# WalkerStalkerv20.net
KiCad netlist of a schematic drawn in EAGLE
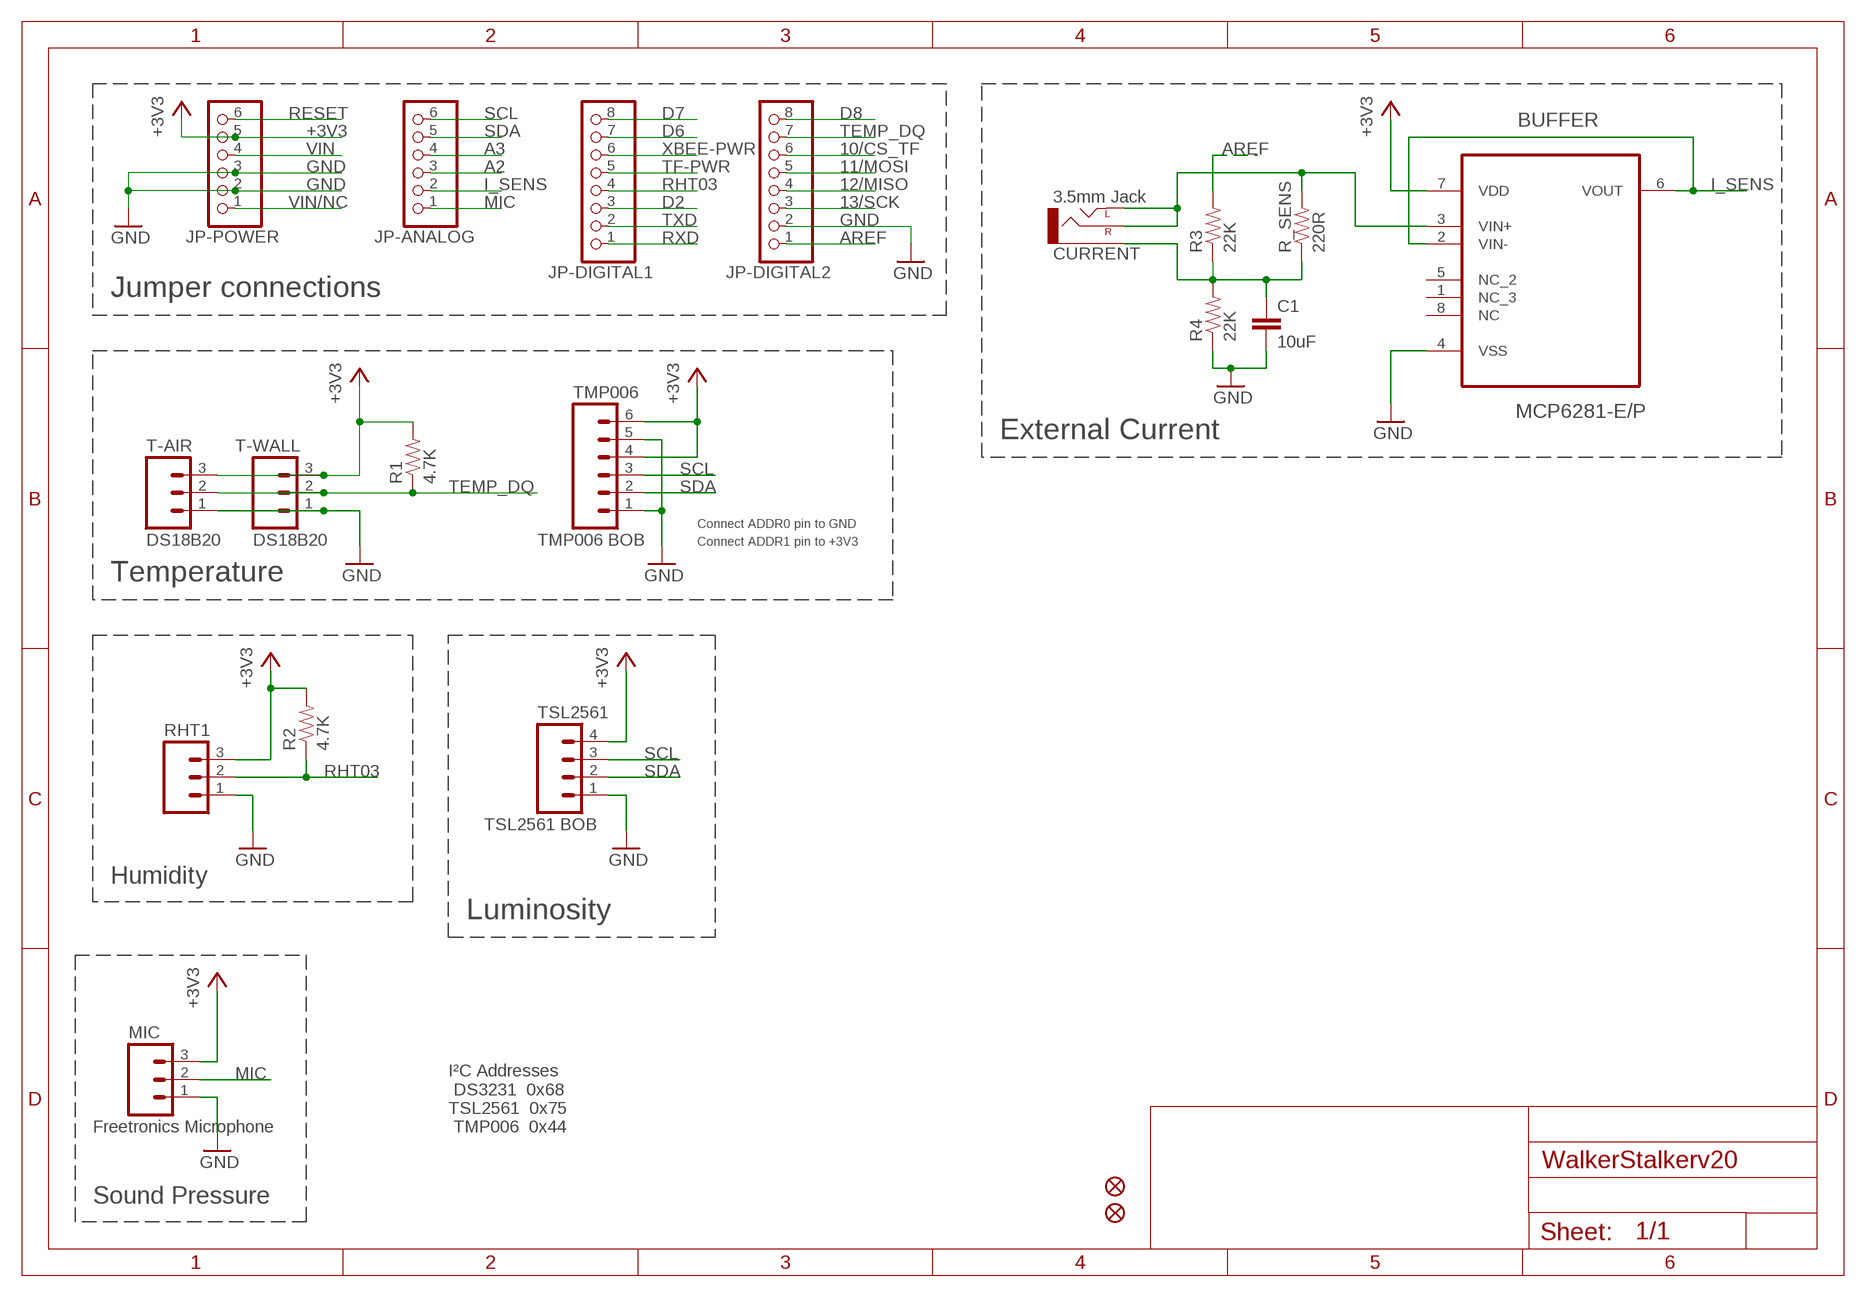
[diagram p0: schematic, sheet 1, part 1 of 2]
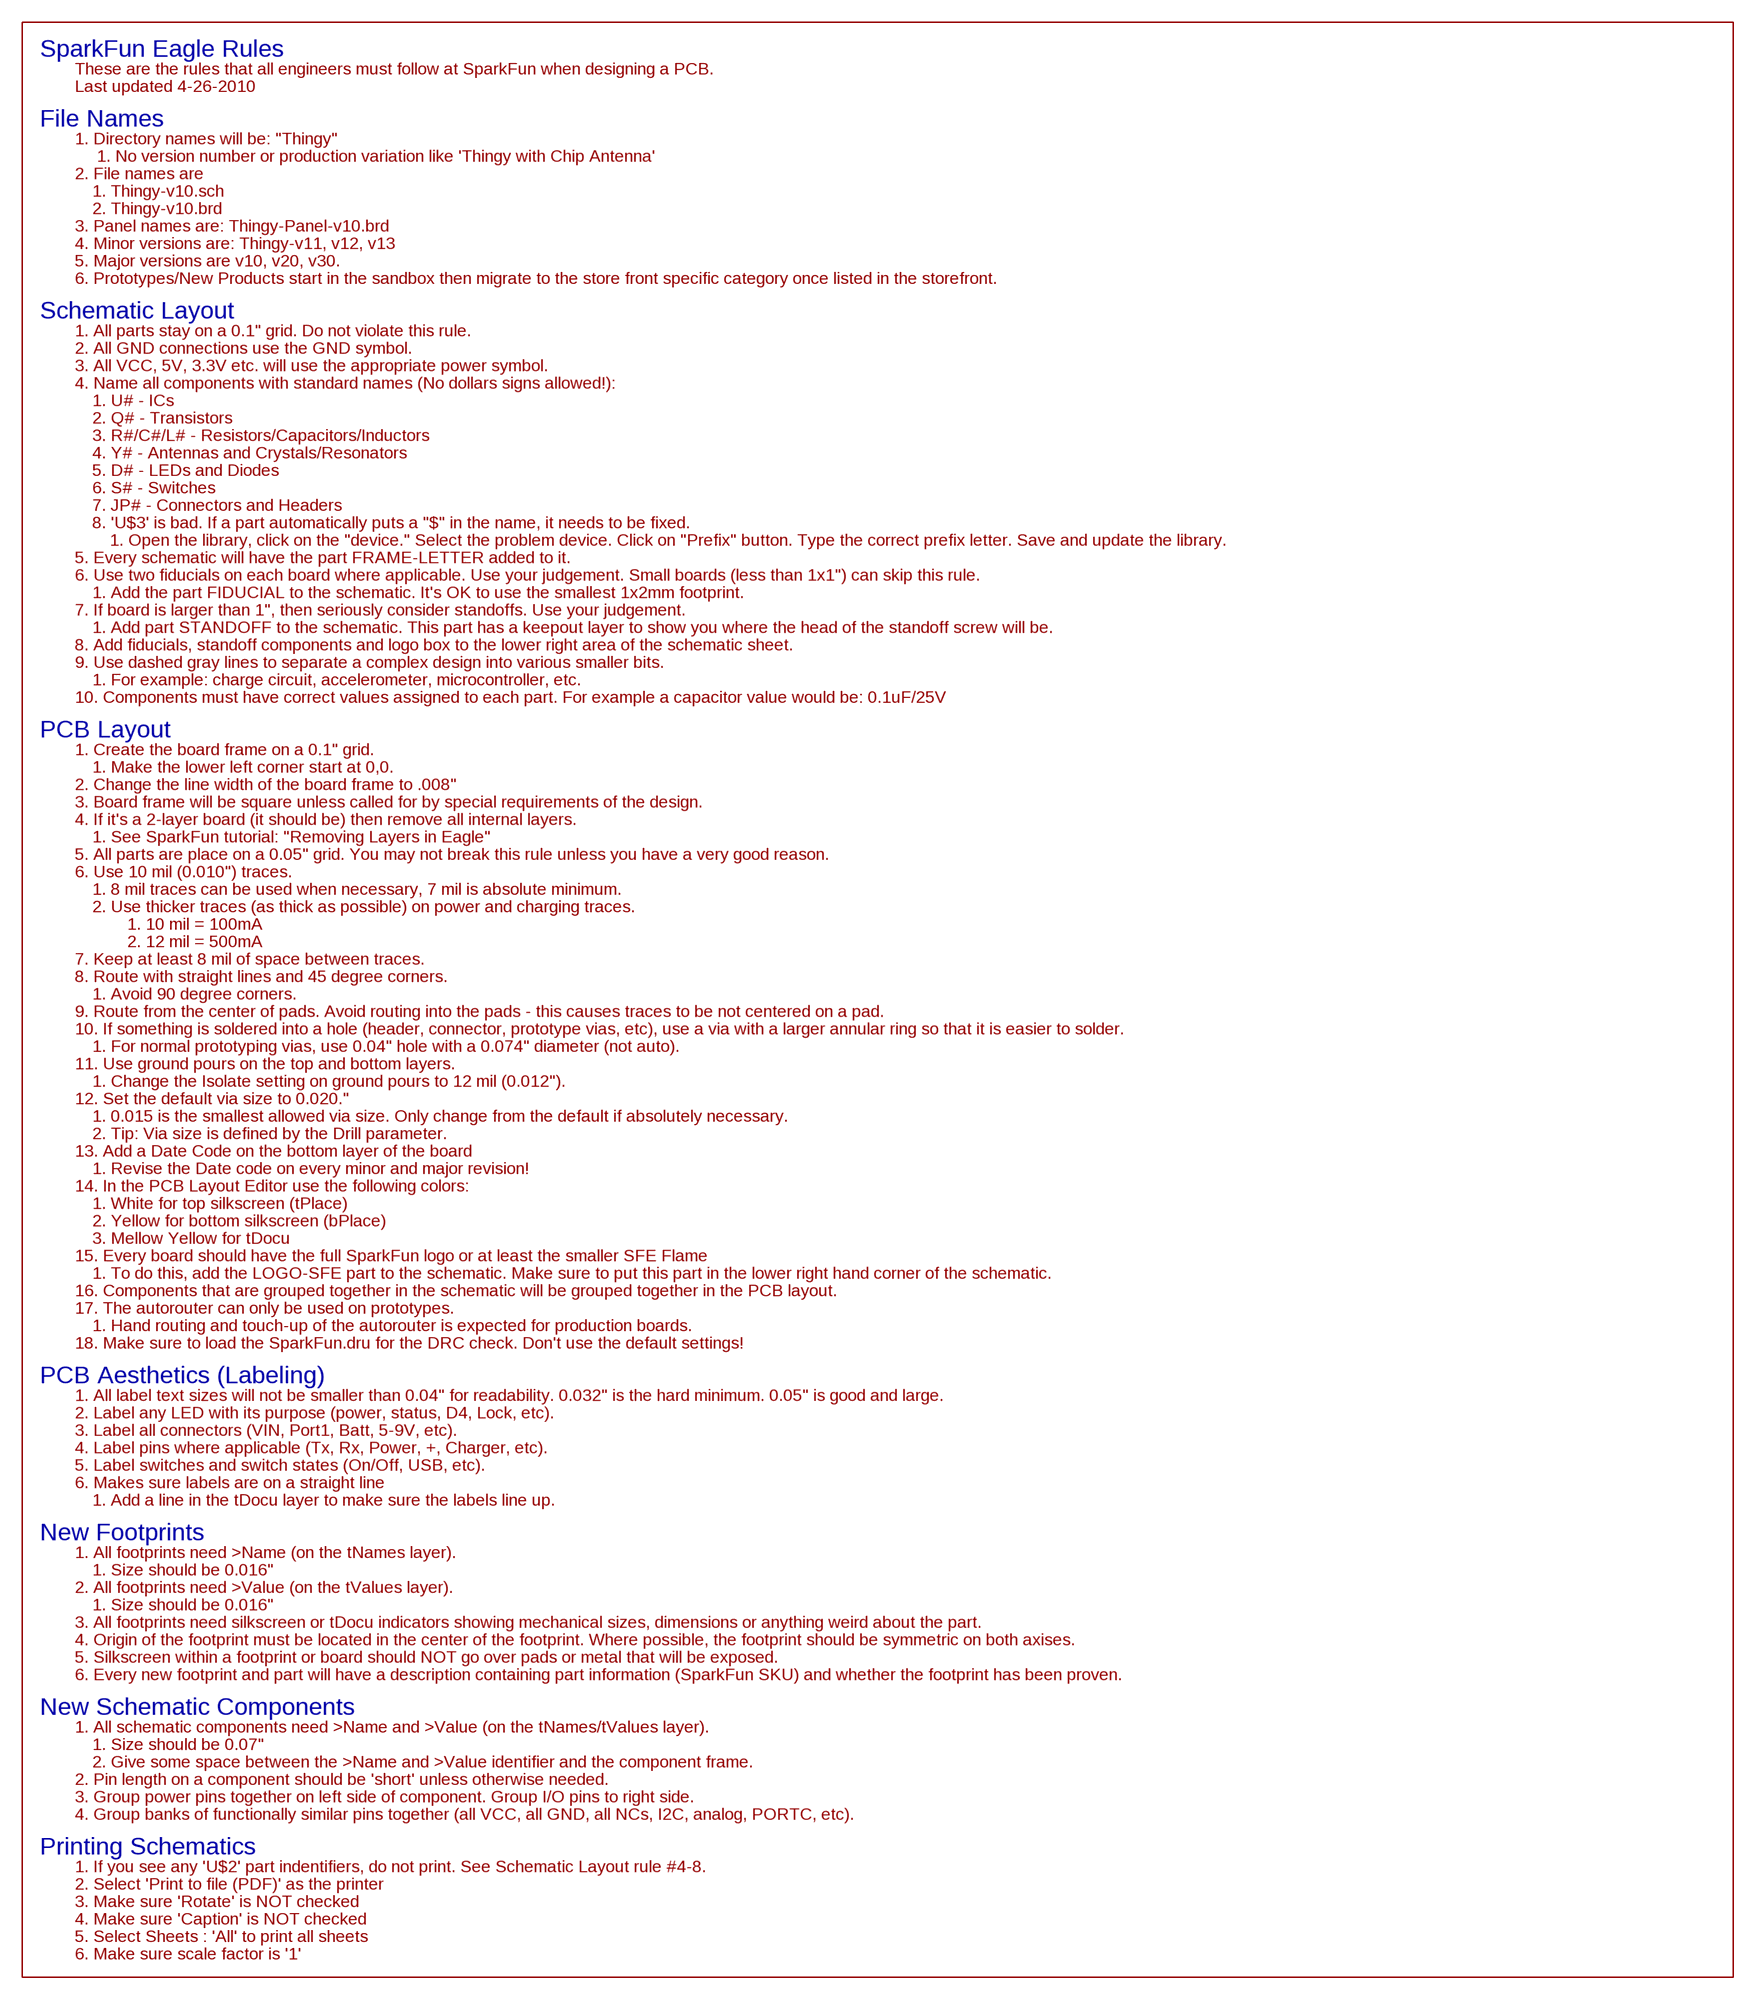
[diagram p1: schematic, sheet 1, part 2 of 2]

(export (version "E")
  (design (tool "Eeschema 10.0.6"))
  (components
    (comp (ref "BUFFER")
      (value "MCP6281-E/P")
      (footprint "eagle-import:DIP254P762X432-8")
      (libsource (lib "eagle-import") (part "MCP6281-E/P"))
    )
    (comp (ref "C1")
      (value "10uF")
      (footprint "eagle-import:1206")
      (libsource (lib "eagle-import") (part "CAP1206"))
    )
    (comp (ref "CURRENT")
      (value "3.5mm Jack")
      (footprint "eagle-import:AUDIO-JACK")
      (libsource (lib "eagle-import") (part "AUDIO-JACKPTH"))
    )
    (comp (ref "FID1")
      (value "FIDUCIAL1.5X3")
      (footprint "eagle-import:FIDUCIAL-1.5X3")
      (libsource (lib "eagle-import") (part "FIDUCIAL1.5X3"))
    )
    (comp (ref "FID2")
      (value "FIDUCIAL1.5X3")
      (footprint "eagle-import:FIDUCIAL-1.5X3")
      (libsource (lib "eagle-import") (part "FIDUCIAL1.5X3"))
    )
    (comp (ref "JP-ANALOG")
      (value "PINHD-1X6CB")
      (footprint "eagle-import:1X06-CLEANBIG")
      (libsource (lib "eagle-import") (part "PINHD-1X6CB"))
    )
    (comp (ref "JP-DIGITAL1")
      (value "PINHD-1X8CLEANBIG")
      (footprint "eagle-import:1X08-CLEANBIG")
      (libsource (lib "eagle-import") (part "PINHD-1X8CLEANBIG"))
    )
    (comp (ref "JP-DIGITAL2")
      (value "PINHD-1X8CLEANBIG")
      (footprint "eagle-import:1X08-CLEANBIG")
      (libsource (lib "eagle-import") (part "PINHD-1X8CLEANBIG"))
    )
    (comp (ref "JP-POWER")
      (value "PINHD-1X6CB")
      (footprint "eagle-import:1X06-CLEANBIG")
      (libsource (lib "eagle-import") (part "PINHD-1X6CB"))
    )
    (comp (ref "MIC")
      (value "Freetronics Microphone")
      (footprint "eagle-import:1X03")
      (libsource (lib "eagle-import") (part "M03PTH"))
    )
    (comp (ref "R1")
      (value "4.7K")
      (footprint "eagle-import:1206")
      (libsource (lib "eagle-import") (part "RESISTOR1206"))
    )
    (comp (ref "R2")
      (value "4.7K")
      (footprint "eagle-import:1206")
      (libsource (lib "eagle-import") (part "RESISTOR1206"))
    )
    (comp (ref "R3")
      (value "22K")
      (footprint "eagle-import:1206")
      (libsource (lib "eagle-import") (part "RESISTOR1206"))
    )
    (comp (ref "R4")
      (value "22K")
      (footprint "eagle-import:1206")
      (libsource (lib "eagle-import") (part "RESISTOR1206"))
    )
    (comp (ref "RHT1")
      (value "RHT03")
      (footprint "eagle-import:1X03")
      (libsource (lib "eagle-import") (part "M03PTH"))
    )
    (comp (ref "R_SENS")
      (value "220R")
      (footprint "eagle-import:1206")
      (libsource (lib "eagle-import") (part "RESISTOR1206"))
    )
    (comp (ref "T-AIR")
      (value "DS18B20")
      (footprint "eagle-import:1X03")
      (libsource (lib "eagle-import") (part "M03PTH"))
    )
    (comp (ref "T-WALL")
      (value "DS18B20")
      (footprint "eagle-import:1X03")
      (libsource (lib "eagle-import") (part "M03PTH"))
    )
    (comp (ref "TMP006")
      (value "TMP006 BOB")
      (footprint "eagle-import:1X06")
      (libsource (lib "eagle-import") (part "M06SIP"))
    )
    (comp (ref "TSL2561")
      (value "TSL2561 BOB")
      (footprint "eagle-import:1X04")
      (libsource (lib "eagle-import") (part "M04PTH"))
    )
  )
  (nets
    (net (code "1") (name "+3V3") (class "Default")
      (node (ref "BUFFER") (pin "7") (pinfunction "VDD_7") (pintype "power_in"))
      (node (ref "JP-POWER") (pin "5") (pinfunction "5_5") (pintype "passive"))
      (node (ref "MIC") (pin "3") (pinfunction "3_3") (pintype "passive"))
      (node (ref "R1") (pin "2") (pinfunction "2_2") (pintype "passive"))
      (node (ref "R2") (pin "2") (pinfunction "2_2") (pintype "passive"))
      (node (ref "RHT1") (pin "3") (pinfunction "3_3") (pintype "passive"))
      (node (ref "T-AIR") (pin "3") (pinfunction "3_3") (pintype "passive"))
      (node (ref "T-WALL") (pin "3") (pinfunction "3_3") (pintype "passive"))
      (node (ref "TMP006") (pin "4") (pinfunction "4_4") (pintype "passive"))
      (node (ref "TMP006") (pin "6") (pinfunction "6_6") (pintype "passive"))
      (node (ref "TSL2561") (pin "4") (pinfunction "4_4") (pintype "passive"))
    )
    (net (code "2") (name "/10{slash}CS_TF") (class "Default")
      (node (ref "JP-DIGITAL2") (pin "6") (pinfunction "6_6") (pintype "passive"))
    )
    (net (code "3") (name "/11{slash}MOSI") (class "Default")
      (node (ref "JP-DIGITAL2") (pin "5") (pinfunction "5_5") (pintype "passive"))
    )
    (net (code "4") (name "/12{slash}MISO") (class "Default")
      (node (ref "JP-DIGITAL2") (pin "4") (pinfunction "4_4") (pintype "passive"))
    )
    (net (code "5") (name "/13{slash}SCK") (class "Default")
      (node (ref "JP-DIGITAL2") (pin "3") (pinfunction "3_3") (pintype "passive"))
    )
    (net (code "6") (name "/A2") (class "Default")
      (node (ref "JP-ANALOG") (pin "3") (pinfunction "3_3") (pintype "passive"))
    )
    (net (code "7") (name "/A3") (class "Default")
      (node (ref "JP-ANALOG") (pin "4") (pinfunction "4_4") (pintype "passive"))
    )
    (net (code "8") (name "/AREF") (class "Default")
      (node (ref "JP-DIGITAL2") (pin "1") (pinfunction "1_1") (pintype "passive"))
      (node (ref "R3") (pin "2") (pinfunction "2_2") (pintype "passive"))
    )
    (net (code "9") (name "/D2") (class "Default")
      (node (ref "JP-DIGITAL1") (pin "3") (pinfunction "3_3") (pintype "passive"))
    )
    (net (code "10") (name "/D6") (class "Default")
      (node (ref "JP-DIGITAL1") (pin "7") (pinfunction "7_7") (pintype "passive"))
    )
    (net (code "11") (name "/D7") (class "Default")
      (node (ref "JP-DIGITAL1") (pin "8") (pinfunction "8_8") (pintype "passive"))
    )
    (net (code "12") (name "/D8") (class "Default")
      (node (ref "JP-DIGITAL2") (pin "8") (pinfunction "8_8") (pintype "passive"))
    )
    (net (code "13") (name "/I_SENS") (class "Default")
      (node (ref "BUFFER") (pin "2") (pinfunction "VIN-_2") (pintype "input"))
      (node (ref "BUFFER") (pin "6") (pinfunction "VOUT_6") (pintype "output"))
      (node (ref "JP-ANALOG") (pin "2") (pinfunction "2_2") (pintype "passive"))
    )
    (net (code "14") (name "/MIC") (class "Default")
      (node (ref "JP-ANALOG") (pin "1") (pinfunction "1_1") (pintype "passive"))
      (node (ref "MIC") (pin "2") (pinfunction "2_2") (pintype "passive"))
    )
    (net (code "15") (name "/RESET") (class "Default")
      (node (ref "JP-POWER") (pin "6") (pinfunction "6_6") (pintype "passive"))
    )
    (net (code "16") (name "/RHT03") (class "Default")
      (node (ref "JP-DIGITAL1") (pin "4") (pinfunction "4_4") (pintype "passive"))
      (node (ref "R2") (pin "1") (pinfunction "1_1") (pintype "passive"))
      (node (ref "RHT1") (pin "2") (pinfunction "2_2") (pintype "passive"))
    )
    (net (code "17") (name "/RXD") (class "Default")
      (node (ref "JP-DIGITAL1") (pin "1") (pinfunction "1_1") (pintype "passive"))
    )
    (net (code "18") (name "/SCL") (class "Default")
      (node (ref "JP-ANALOG") (pin "6") (pinfunction "6_6") (pintype "passive"))
      (node (ref "TMP006") (pin "3") (pinfunction "3_3") (pintype "passive"))
      (node (ref "TSL2561") (pin "3") (pinfunction "3_3") (pintype "passive"))
    )
    (net (code "19") (name "/SDA") (class "Default")
      (node (ref "JP-ANALOG") (pin "5") (pinfunction "5_5") (pintype "passive"))
      (node (ref "TMP006") (pin "2") (pinfunction "2_2") (pintype "passive"))
      (node (ref "TSL2561") (pin "2") (pinfunction "2_2") (pintype "passive"))
    )
    (net (code "20") (name "/TEMP_DQ") (class "Default")
      (node (ref "JP-DIGITAL2") (pin "7") (pinfunction "7_7") (pintype "passive"))
      (node (ref "R1") (pin "1") (pinfunction "1_1") (pintype "passive"))
      (node (ref "T-AIR") (pin "2") (pinfunction "2_2") (pintype "passive"))
      (node (ref "T-WALL") (pin "2") (pinfunction "2_2") (pintype "passive"))
    )
    (net (code "21") (name "/TF-PWR") (class "Default")
      (node (ref "JP-DIGITAL1") (pin "5") (pinfunction "5_5") (pintype "passive"))
    )
    (net (code "22") (name "/TXD") (class "Default")
      (node (ref "JP-DIGITAL1") (pin "2") (pinfunction "2_2") (pintype "passive"))
    )
    (net (code "23") (name "/VIN") (class "Default")
      (node (ref "JP-POWER") (pin "4") (pinfunction "4_4") (pintype "passive"))
    )
    (net (code "24") (name "/VIN{slash}NC") (class "Default")
      (node (ref "JP-POWER") (pin "1") (pinfunction "1_1") (pintype "passive"))
    )
    (net (code "25") (name "/XBEE-PWR") (class "Default")
      (node (ref "JP-DIGITAL1") (pin "6") (pinfunction "6_6") (pintype "passive"))
    )
    (net (code "26") (name "GND") (class "Default")
      (node (ref "BUFFER") (pin "4") (pinfunction "VSS_4") (pintype "power_in"))
      (node (ref "C1") (pin "2") (pinfunction "2_2") (pintype "passive"))
      (node (ref "JP-DIGITAL2") (pin "2") (pinfunction "2_2") (pintype "passive"))
      (node (ref "JP-POWER") (pin "2") (pinfunction "2_2") (pintype "passive"))
      (node (ref "JP-POWER") (pin "3") (pinfunction "3_3") (pintype "passive"))
      (node (ref "MIC") (pin "1") (pinfunction "1_1") (pintype "passive"))
      (node (ref "R4") (pin "1") (pinfunction "1_1") (pintype "passive"))
      (node (ref "RHT1") (pin "1") (pinfunction "1_1") (pintype "passive"))
      (node (ref "T-AIR") (pin "1") (pinfunction "1_1") (pintype "passive"))
      (node (ref "T-WALL") (pin "1") (pinfunction "1_1") (pintype "passive"))
      (node (ref "TMP006") (pin "1") (pinfunction "1_1") (pintype "passive"))
      (node (ref "TMP006") (pin "5") (pinfunction "5_5") (pintype "passive"))
      (node (ref "TSL2561") (pin "1") (pinfunction "1_1") (pintype "passive"))
    )
    (net (code "27") (name "Net-(BUFFER-VIN+)") (class "Default")
      (node (ref "BUFFER") (pin "3") (pinfunction "VIN+_3") (pintype "input"))
      (node (ref "CURRENT") (pin "RING") (pinfunction "RIGHT_RING") (pintype "bidirectional"))
      (node (ref "CURRENT") (pin "TIP") (pinfunction "LEFT_TIP") (pintype "bidirectional"))
      (node (ref "R_SENS") (pin "2") (pinfunction "2_2") (pintype "passive"))
    )
    (net (code "28") (name "Net-(C1-Pad1)") (class "Default")
      (node (ref "C1") (pin "1") (pinfunction "1_1") (pintype "passive"))
      (node (ref "CURRENT") (pin "SLEEVE") (pinfunction "SLEEVE_SLEEVE") (pintype "bidirectional"))
      (node (ref "R3") (pin "1") (pinfunction "1_1") (pintype "passive"))
      (node (ref "R4") (pin "2") (pinfunction "2_2") (pintype "passive"))
      (node (ref "R_SENS") (pin "1") (pinfunction "1_1") (pintype "passive"))
    )
    (net (code "29") (name "unconnected-(BUFFER-NC-Pad8)") (class "Default")
      (node (ref "BUFFER") (pin "8") (pinfunction "NC_8") (pintype "no_connect"))
    )
    (net (code "30") (name "unconnected-(BUFFER-NC_2-Pad5)") (class "Default")
      (node (ref "BUFFER") (pin "5") (pinfunction "NC_2_5") (pintype "no_connect"))
    )
    (net (code "31") (name "unconnected-(BUFFER-NC_3-Pad1)") (class "Default")
      (node (ref "BUFFER") (pin "1") (pinfunction "NC_3_1") (pintype "no_connect"))
    )
  )
)
